# SparkFun_NanoBeacon_Production_Board_-_I.net
KiCad netlist of a schematic drawn in EAGLE
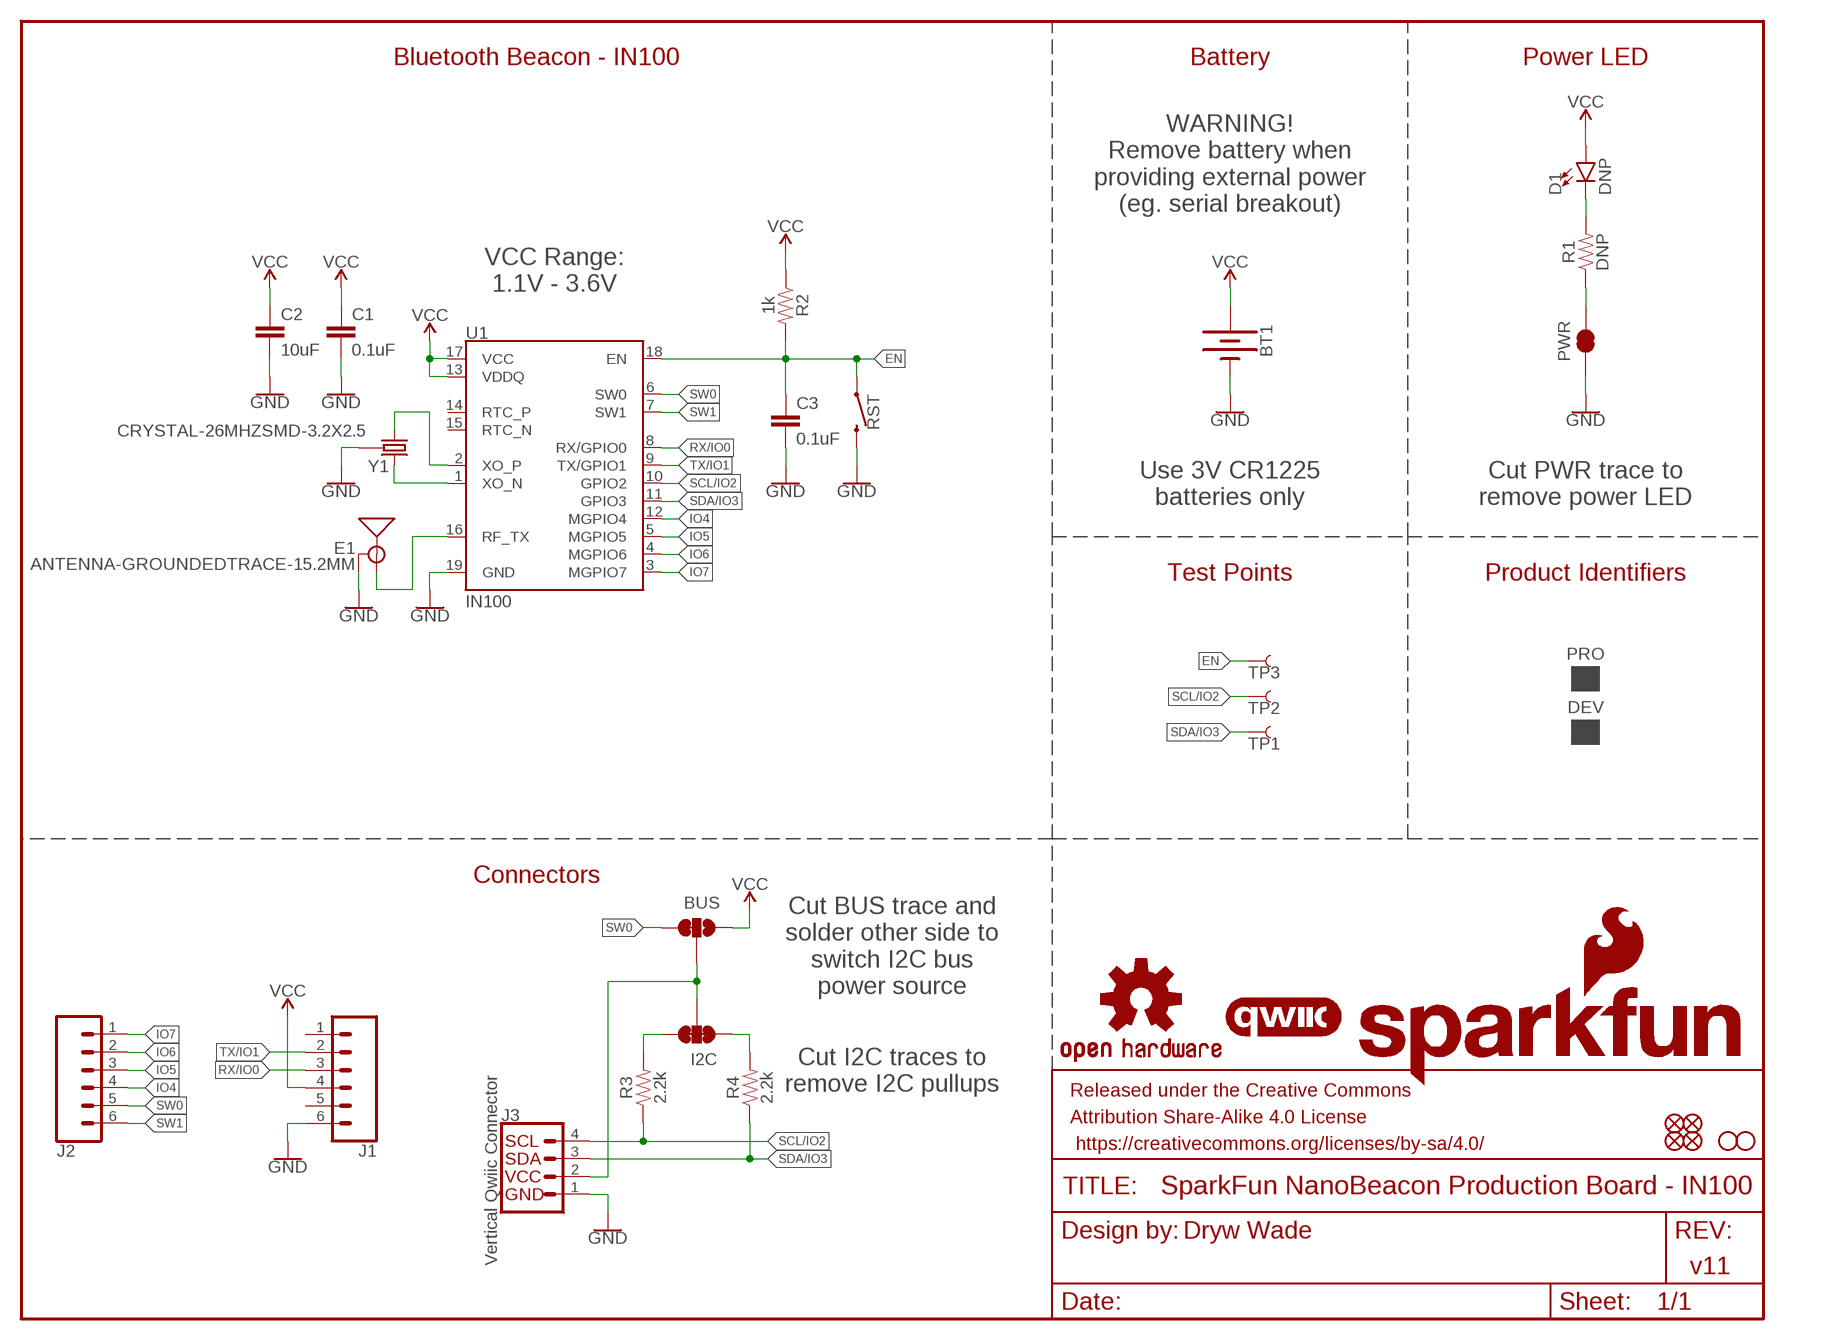
[diagram p0: schematic, sheet 1]

(export (version "E")
  (design (tool "Eeschema 10.0.6"))
  (components
    (comp (ref "BT1")
      (value "BATTERY-12MM_SMD")
      (footprint "eagle-import:BATTCON_12MM")
      (libsource (lib "eagle-import") (part "BATTERY-12MM_SMD"))
    )
    (comp (ref "BUS")
      (value "JUMPER-SMT_3_1-NC_TRACE_SILK")
      (footprint "eagle-import:SMT-JUMPER_3_1-NC_TRACE_SILK")
      (libsource (lib "eagle-import") (part "JUMPER-SMT_3_1-NC_TRACE_SILK"))
    )
    (comp (ref "C1")
      (value "0.1uF")
      (footprint "eagle-import:0402-TIGHT")
      (libsource (lib "eagle-import") (part "0.1UF-0402T-6.3V-10%-X7R"))
    )
    (comp (ref "C2")
      (value "10uF")
      (footprint "eagle-import:0402-TIGHT")
      (libsource (lib "eagle-import") (part "10UF-0402T-6.3V-20%"))
    )
    (comp (ref "C3")
      (value "0.1uF")
      (footprint "eagle-import:0402-TIGHT")
      (libsource (lib "eagle-import") (part "0.1UF-0402T-6.3V-10%-X7R"))
    )
    (comp (ref "D1")
      (value "DNP")
      (footprint "eagle-import:LED-0402")
      (libsource (lib "eagle-import") (part "LED-RED_0402"))
    )
    (comp (ref "DEV")
      (value "PROD_ID_PASTE_SILK")
      (footprint "eagle-import:PRODUCT_IDENT_PASTE_SILK")
      (libsource (lib "eagle-import") (part "PROD_ID_PASTE_SILK"))
    )
    (comp (ref "E1")
      (value "ANTENNA-GROUNDEDTRACE-15.2MM")
      (footprint "eagle-import:TRACE_ANTENNA_2.4GHZ_15.2MM")
      (libsource (lib "eagle-import") (part "ANTENNA-GROUNDEDTRACE-15.2MM"))
    )
    (comp (ref "FD1")
      (value "FIDUCIAL1X2")
      (footprint "eagle-import:FIDUCIAL-1X2")
      (libsource (lib "eagle-import") (part "FIDUCIAL1X2"))
    )
    (comp (ref "FD2")
      (value "FIDUCIAL1X2")
      (footprint "eagle-import:FIDUCIAL-1X2")
      (libsource (lib "eagle-import") (part "FIDUCIAL1X2"))
    )
    (comp (ref "FD3")
      (value "FIDUCIAL1X2")
      (footprint "eagle-import:FIDUCIAL-1X2")
      (libsource (lib "eagle-import") (part "FIDUCIAL1X2"))
    )
    (comp (ref "FD4")
      (value "FIDUCIAL1X2")
      (footprint "eagle-import:FIDUCIAL-1X2")
      (libsource (lib "eagle-import") (part "FIDUCIAL1X2"))
    )
    (comp (ref "FRAME1")
      (value "FRAME-LETTER")
      (footprint "eagle-import:CREATIVE_COMMONS")
      (libsource (lib "eagle-import") (part "FRAME-LETTER"))
    )
    (comp (ref "H1")
      (value "STAND-OFF")
      (footprint "eagle-import:STAND-OFF")
      (libsource (lib "eagle-import") (part "STAND-OFF"))
    )
    (comp (ref "H2")
      (value "STAND-OFF")
      (footprint "eagle-import:STAND-OFF")
      (libsource (lib "eagle-import") (part "STAND-OFF"))
    )
    (comp (ref "I2C")
      (value "JUMPER-SMT_3_2-NC_TRACE_SILK")
      (footprint "eagle-import:SMT-JUMPER_3_2-NC_TRACE_SILK")
      (libsource (lib "eagle-import") (part "JUMPER-SMT_3_2-NC_TRACE_SILK"))
    )
    (comp (ref "J1")
      (value "CONN_06NO_SILK_NO_POP")
      (footprint "eagle-import:1X06_NO_SILK")
      (libsource (lib "eagle-import") (part "CONN_06NO_SILK_NO_POP"))
    )
    (comp (ref "J2")
      (value "CONN_06NO_SILK_NO_POP")
      (footprint "eagle-import:1X06_NO_SILK")
      (libsource (lib "eagle-import") (part "CONN_06NO_SILK_NO_POP"))
    )
    (comp (ref "J3")
      (value "Vertical Qwiic Connector")
      (footprint "eagle-import:JST04_1MM_VERT")
      (libsource (lib "eagle-import") (part "QWIIC_CONNECTOR"))
    )
    (comp (ref "LOGO1")
      (value "OSHW-LOGOS")
      (footprint "eagle-import:OSHW-LOGO-S")
      (libsource (lib "eagle-import") (part "OSHW-LOGOS"))
    )
    (comp (ref "LOGO2")
      (value "SFE_LOGO_NAME_FLAME.1_INCH")
      (footprint "eagle-import:SFE_LOGO_NAME_FLAME_.1")
      (libsource (lib "eagle-import") (part "SFE_LOGO_NAME_FLAME.1_INCH"))
    )
    (comp (ref "LOGO3")
      (value "QWIIC_LOGO_3MM")
      (footprint "eagle-import:QWIIC_3MM")
      (libsource (lib "eagle-import") (part "QWIIC_LOGO_3MM"))
    )
    (comp (ref "PRO")
      (value "PROD_ID_PASTE_SILK")
      (footprint "eagle-import:PRODUCT_IDENT_PASTE_SILK")
      (libsource (lib "eagle-import") (part "PROD_ID_PASTE_SILK"))
    )
    (comp (ref "PWR")
      (value "JUMPER-SMT_2_NC_TRACE_SILK")
      (footprint "eagle-import:SMT-JUMPER_2_NC_TRACE_SILK")
      (libsource (lib "eagle-import") (part "JUMPER-SMT_2_NC_TRACE_SILK"))
    )
    (comp (ref "R1")
      (value "DNP")
      (footprint "eagle-import:0402-TIGHT")
      (libsource (lib "eagle-import") (part "2.2KOHM-0402T-1/16W-1%"))
    )
    (comp (ref "R2")
      (value "1k")
      (footprint "eagle-import:0402-TIGHT")
      (libsource (lib "eagle-import") (part "1KOHM-0402T-1/16W-1%"))
    )
    (comp (ref "R3")
      (value "2.2k")
      (footprint "eagle-import:0402-TIGHT")
      (libsource (lib "eagle-import") (part "2.2KOHM-0402T-1/16W-1%"))
    )
    (comp (ref "R4")
      (value "2.2k")
      (footprint "eagle-import:0402-TIGHT")
      (libsource (lib "eagle-import") (part "2.2KOHM-0402T-1/16W-1%"))
    )
    (comp (ref "RST")
      (value "DNP")
      (footprint "eagle-import:TACTILE_SWITCH_SMD_4.6X2.8MM")
      (libsource (lib "eagle-import") (part "MOMENTARY-SWITCH-SPST-SMD-4.6X2.8MM"))
    )
    (comp (ref "TP1")
      (value "TEST-POINT3")
      (footprint "eagle-import:PAD.03X.03")
      (libsource (lib "eagle-import") (part "TEST-POINT3"))
    )
    (comp (ref "TP2")
      (value "TEST-POINT3")
      (footprint "eagle-import:PAD.03X.03")
      (libsource (lib "eagle-import") (part "TEST-POINT3"))
    )
    (comp (ref "TP3")
      (value "TEST-POINT3")
      (footprint "eagle-import:PAD.03X.03")
      (libsource (lib "eagle-import") (part "TEST-POINT3"))
    )
    (comp (ref "U1")
      (value "IN100")
      (footprint "eagle-import:IN100")
      (libsource (lib "eagle-import") (part "IN100"))
    )
    (comp (ref "Y1")
      (value "CRYSTAL-26MHZSMD-3.2X2.5")
      (footprint "eagle-import:CRYSTAL-SMD-3.2X2.5MM")
      (libsource (lib "eagle-import") (part "CRYSTAL-26MHZSMD-3.2X2.5"))
    )
  )
  (nets
    (net (code "1") (name "EN") (class "Default")
      (node (ref "C3") (pin "1") (pinfunction "1_1") (pintype "passive"))
      (node (ref "R2") (pin "2") (pinfunction "2_2") (pintype "passive"))
      (node (ref "RST") (pin "1") (pinfunction "1_1") (pintype "passive"))
      (node (ref "RST") (pin "2") (pinfunction "1_2") (pintype "passive"))
      (node (ref "TP3") (pin "1") (pinfunction "1_1") (pintype "bidirectional"))
      (node (ref "U1") (pin "18") (pinfunction "EN_18") (pintype "input"))
    )
    (net (code "2") (name "GND") (class "Default")
      (node (ref "BT1") (pin "GND") (pinfunction "-_GND") (pintype "power_in"))
      (node (ref "C1") (pin "2") (pinfunction "2_2") (pintype "passive"))
      (node (ref "C2") (pin "2") (pinfunction "2_2") (pintype "passive"))
      (node (ref "C3") (pin "2") (pinfunction "2_2") (pintype "passive"))
      (node (ref "E1") (pin "GND") (pinfunction "GND_GND") (pintype "bidirectional"))
      (node (ref "J1") (pin "6") (pinfunction "6_6") (pintype "passive"))
      (node (ref "J3") (pin "1") (pinfunction "1_1") (pintype "power_in"))
      (node (ref "PWR") (pin "1") (pinfunction "1_1") (pintype "passive"))
      (node (ref "RST") (pin "3") (pinfunction "2_3") (pintype "passive"))
      (node (ref "RST") (pin "4") (pinfunction "2_4") (pintype "passive"))
      (node (ref "U1") (pin "19") (pinfunction "GND_19") (pintype "power_in"))
      (node (ref "Y1") (pin "2") (pinfunction "GND_2") (pintype "power_in"))
      (node (ref "Y1") (pin "4") (pinfunction "GND_4") (pintype "power_in"))
    )
    (net (code "3") (name "IO4") (class "Default")
      (node (ref "J2") (pin "4") (pinfunction "4_4") (pintype "passive"))
      (node (ref "U1") (pin "12") (pinfunction "MGPIO4_12") (pintype "bidirectional"))
    )
    (net (code "4") (name "IO5") (class "Default")
      (node (ref "J2") (pin "3") (pinfunction "3_3") (pintype "passive"))
      (node (ref "U1") (pin "5") (pinfunction "MGPIO5_5") (pintype "bidirectional"))
    )
    (net (code "5") (name "IO6") (class "Default")
      (node (ref "J2") (pin "2") (pinfunction "2_2") (pintype "passive"))
      (node (ref "U1") (pin "4") (pinfunction "MGPIO6_4") (pintype "bidirectional"))
    )
    (net (code "6") (name "IO7") (class "Default")
      (node (ref "J2") (pin "1") (pinfunction "1_1") (pintype "passive"))
      (node (ref "U1") (pin "3") (pinfunction "MGPIO7_3") (pintype "bidirectional"))
    )
    (net (code "7") (name "Net-(BUS-Pad2)") (class "Default")
      (node (ref "BUS") (pin "2") (pinfunction "2_2") (pintype "passive"))
      (node (ref "I2C") (pin "2") (pinfunction "2_2") (pintype "passive"))
      (node (ref "J3") (pin "2") (pinfunction "2_2") (pintype "power_in"))
    )
    (net (code "8") (name "Net-(D1-PadC)") (class "Default")
      (node (ref "D1") (pin "C") (pinfunction "C_C") (pintype "passive"))
      (node (ref "R1") (pin "2") (pinfunction "2_2") (pintype "passive"))
    )
    (net (code "9") (name "Net-(E1-SIGNAL)") (class "Default")
      (node (ref "E1") (pin "ANT") (pinfunction "SIGNAL_ANT") (pintype "bidirectional"))
      (node (ref "U1") (pin "16") (pinfunction "RF_TX_16") (pintype "bidirectional"))
    )
    (net (code "10") (name "Net-(I2C-Pad1)") (class "Default")
      (node (ref "I2C") (pin "1") (pinfunction "1_1") (pintype "passive"))
      (node (ref "R4") (pin "2") (pinfunction "2_2") (pintype "passive"))
    )
    (net (code "11") (name "Net-(I2C-Pad3)") (class "Default")
      (node (ref "I2C") (pin "3") (pinfunction "3_3") (pintype "passive"))
      (node (ref "R3") (pin "2") (pinfunction "2_2") (pintype "passive"))
    )
    (net (code "12") (name "Net-(PWR-Pad2)") (class "Default")
      (node (ref "PWR") (pin "2") (pinfunction "2_2") (pintype "passive"))
      (node (ref "R1") (pin "1") (pinfunction "1_1") (pintype "passive"))
    )
    (net (code "13") (name "Net-(U1-XO_N)") (class "Default")
      (node (ref "U1") (pin "1") (pinfunction "XO_N_1") (pintype "bidirectional"))
      (node (ref "Y1") (pin "3") (pinfunction "2_3") (pintype "passive"))
    )
    (net (code "14") (name "Net-(U1-XO_P)") (class "Default")
      (node (ref "U1") (pin "2") (pinfunction "XO_P_2") (pintype "bidirectional"))
      (node (ref "Y1") (pin "1") (pinfunction "1_1") (pintype "passive"))
    )
    (net (code "15") (name "RX{slash}IO0") (class "Default")
      (node (ref "J1") (pin "3") (pinfunction "3_3") (pintype "passive"))
      (node (ref "U1") (pin "8") (pinfunction "RX/GPIO0_8") (pintype "bidirectional"))
    )
    (net (code "16") (name "SCL{slash}IO2") (class "Default")
      (node (ref "J3") (pin "4") (pinfunction "4_4") (pintype "passive"))
      (node (ref "R3") (pin "1") (pinfunction "1_1") (pintype "passive"))
      (node (ref "TP2") (pin "1") (pinfunction "1_1") (pintype "bidirectional"))
      (node (ref "U1") (pin "10") (pinfunction "GPIO2_10") (pintype "bidirectional"))
    )
    (net (code "17") (name "SDA{slash}IO3") (class "Default")
      (node (ref "J3") (pin "3") (pinfunction "3_3") (pintype "passive"))
      (node (ref "R4") (pin "1") (pinfunction "1_1") (pintype "passive"))
      (node (ref "TP1") (pin "1") (pinfunction "1_1") (pintype "bidirectional"))
      (node (ref "U1") (pin "11") (pinfunction "GPIO3_11") (pintype "bidirectional"))
    )
    (net (code "18") (name "SW0") (class "Default")
      (node (ref "BUS") (pin "3") (pinfunction "3_3") (pintype "passive"))
      (node (ref "J2") (pin "5") (pinfunction "5_5") (pintype "passive"))
      (node (ref "U1") (pin "6") (pinfunction "SW0_6") (pintype "output"))
    )
    (net (code "19") (name "SW1") (class "Default")
      (node (ref "J2") (pin "6") (pinfunction "6_6") (pintype "passive"))
      (node (ref "U1") (pin "7") (pinfunction "SW1_7") (pintype "output"))
    )
    (net (code "20") (name "TX{slash}IO1") (class "Default")
      (node (ref "J1") (pin "2") (pinfunction "2_2") (pintype "passive"))
      (node (ref "U1") (pin "9") (pinfunction "TX/GPIO1_9") (pintype "bidirectional"))
    )
    (net (code "21") (name "VCC") (class "Default")
      (node (ref "BT1") (pin "PWR@1") (pinfunction "+_PWR@1") (pintype "power_in"))
      (node (ref "BT1") (pin "PWR@2") (pinfunction "+_PWR@2") (pintype "power_in"))
      (node (ref "BUS") (pin "1") (pinfunction "1_1") (pintype "passive"))
      (node (ref "C1") (pin "1") (pinfunction "1_1") (pintype "passive"))
      (node (ref "C2") (pin "1") (pinfunction "1_1") (pintype "passive"))
      (node (ref "D1") (pin "A") (pinfunction "A_A") (pintype "passive"))
      (node (ref "J1") (pin "4") (pinfunction "4_4") (pintype "passive"))
      (node (ref "R2") (pin "1") (pinfunction "1_1") (pintype "passive"))
      (node (ref "U1") (pin "13") (pinfunction "VDDQ_13") (pintype "power_in"))
      (node (ref "U1") (pin "17") (pinfunction "VCC_17") (pintype "power_in"))
    )
    (net (code "22") (name "unconnected-(J1-Pad1)") (class "Default")
      (node (ref "J1") (pin "1") (pinfunction "1_1") (pintype "passive"))
    )
    (net (code "23") (name "unconnected-(J1-Pad5)") (class "Default")
      (node (ref "J1") (pin "5") (pinfunction "5_5") (pintype "passive"))
    )
    (net (code "24") (name "unconnected-(U1-RTC_N-Pad15)") (class "Default")
      (node (ref "U1") (pin "15") (pinfunction "RTC_N_15") (pintype "bidirectional"))
    )
    (net (code "25") (name "unconnected-(U1-RTC_P-Pad14)") (class "Default")
      (node (ref "U1") (pin "14") (pinfunction "RTC_P_14") (pintype "bidirectional"))
    )
  )
)
